# EEG_main.net
KiCad netlist of a schematic drawn in Altium Designer
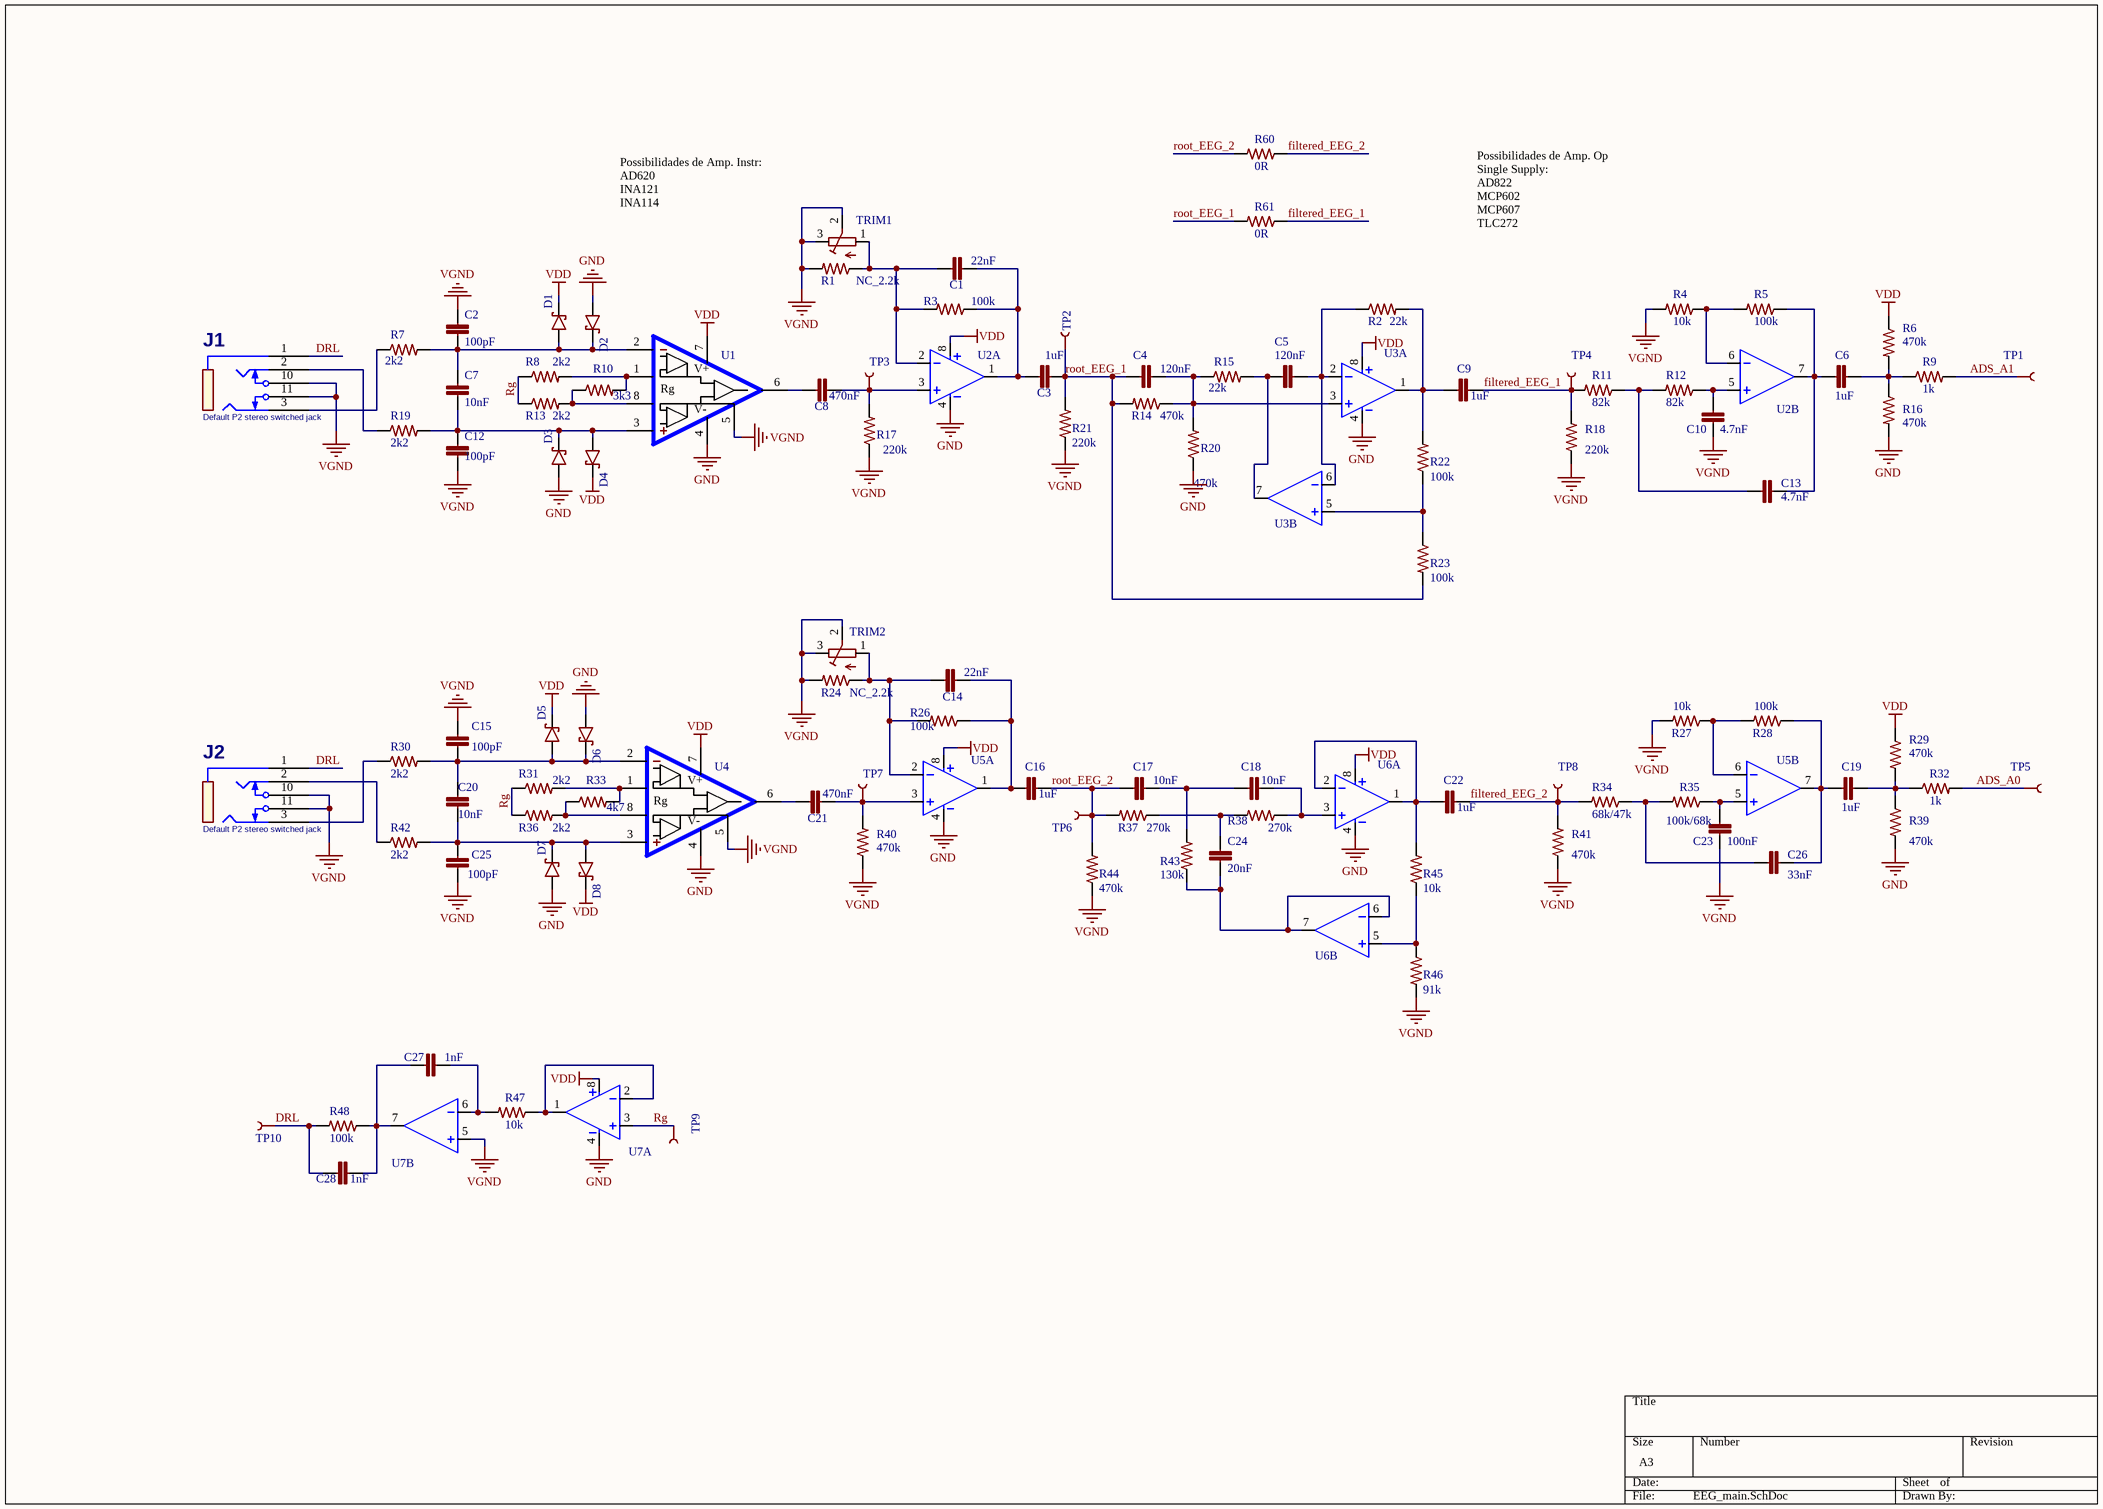
[diagram p0: EEG_main.SchDoc]

(export (version "E")
  (design (tool "Eeschema 10.0.6"))
  (components
    (comp (ref "C1")
      (value "22nF")
      (footprint "C0805 - rounded")
      (description "Generic Capacitor SMD")
      (libsource (lib "rcl") (part "C-EU-SMD"))
    )
    (comp (ref "C2")
      (value "100pF")
      (footprint "C0805 - rounded")
      (description "Generic Capacitor SMD")
      (libsource (lib "") (part "C-EU-SMD_1"))
    )
    (comp (ref "C3")
      (value "1uF")
      (footprint "C0805 - rounded")
      (description "Generic Capacitor SMD")
      (libsource (lib "rcl") (part "C-EU-SMD"))
    )
    (comp (ref "C4")
      (value "120nF")
      (footprint "C0805 - rounded")
      (description "Generic Capacitor SMD")
      (libsource (lib "rcl") (part "C-EU-SMD"))
    )
    (comp (ref "C5")
      (value "120nF")
      (footprint "C0805 - rounded")
      (description "Generic Capacitor SMD")
      (libsource (lib "rcl") (part "C-EU-SMD"))
    )
    (comp (ref "C6")
      (value "1uF")
      (footprint "C0805 - rounded")
      (description "Generic Capacitor SMD")
      (libsource (lib "rcl") (part "C-EU-SMD"))
    )
    (comp (ref "C7")
      (value "10nF")
      (footprint "C0805 - rounded")
      (description "Generic Capacitor SMD")
      (libsource (lib "") (part "C-EU-SMD_1"))
    )
    (comp (ref "C8")
      (value "470nF")
      (footprint "C0805 - rounded")
      (description "Generic Capacitor SMD")
      (libsource (lib "rcl") (part "C-EU-SMD"))
    )
    (comp (ref "C9")
      (value "1uF")
      (footprint "C0805 - rounded")
      (description "Generic Capacitor SMD")
      (libsource (lib "rcl") (part "C-EU-SMD"))
    )
    (comp (ref "C10")
      (value "4.7nF")
      (footprint "C0805 - rounded")
      (description "Generic Capacitor SMD")
      (libsource (lib "") (part "C-EU-SMD_1"))
    )
    (comp (ref "C12")
      (value "100pF")
      (footprint "C0805 - rounded")
      (description "Generic Capacitor SMD")
      (libsource (lib "") (part "C-EU-SMD_3"))
    )
    (comp (ref "C13")
      (value "4.7nF")
      (footprint "C0805 - rounded")
      (description "Generic Capacitor SMD")
      (libsource (lib "") (part "C-EU-SMD_2"))
    )
    (comp (ref "C14")
      (value "22nF")
      (footprint "C0805 - rounded")
      (description "Generic Capacitor SMD")
      (libsource (lib "rcl") (part "C-EU-SMD"))
    )
    (comp (ref "C15")
      (value "100pF")
      (footprint "C0805 - rounded")
      (description "Generic Capacitor SMD")
      (libsource (lib "") (part "C-EU-SMD_1"))
    )
    (comp (ref "C16")
      (value "1uF")
      (footprint "C0805 - rounded")
      (description "Generic Capacitor SMD")
      (libsource (lib "rcl") (part "C-EU-SMD"))
    )
    (comp (ref "C17")
      (value "10nF")
      (footprint "C0805 - rounded")
      (description "Generic Capacitor SMD")
      (libsource (lib "rcl") (part "C-EU-SMD"))
    )
    (comp (ref "C18")
      (value "10nF")
      (footprint "C0805 - rounded")
      (description "Generic Capacitor SMD")
      (libsource (lib "rcl") (part "C-EU-SMD"))
    )
    (comp (ref "C19")
      (value "1uF")
      (footprint "C0805 - rounded")
      (description "Generic Capacitor SMD")
      (libsource (lib "rcl") (part "C-EU-SMD"))
    )
    (comp (ref "C20")
      (value "10nF")
      (footprint "C0805 - rounded")
      (description "Generic Capacitor SMD")
      (libsource (lib "") (part "C-EU-SMD_1"))
    )
    (comp (ref "C21")
      (value "470nF")
      (footprint "C0805 - rounded")
      (description "Generic Capacitor SMD")
      (libsource (lib "rcl") (part "C-EU-SMD"))
    )
    (comp (ref "C22")
      (value "1uF")
      (footprint "C0805 - rounded")
      (description "Generic Capacitor SMD")
      (libsource (lib "rcl") (part "C-EU-SMD"))
    )
    (comp (ref "C23")
      (value "100nF")
      (footprint "C0805 - rounded")
      (description "Generic Capacitor SMD")
      (libsource (lib "") (part "C-EU-SMD_1"))
    )
    (comp (ref "C24")
      (value "20nF")
      (footprint "C0805 - rounded")
      (description "Generic Capacitor SMD")
      (libsource (lib "") (part "C-EU-SMD_1"))
    )
    (comp (ref "C25")
      (value "100pF")
      (footprint "C0805 - rounded")
      (description "Generic Capacitor SMD")
      (libsource (lib "") (part "C-EU-SMD_3"))
    )
    (comp (ref "C26")
      (value "33nF")
      (footprint "C0805 - rounded")
      (description "Generic Capacitor SMD")
      (libsource (lib "") (part "C-EU-SMD_2"))
    )
    (comp (ref "C27")
      (value "1nF")
      (footprint "C0805 - rounded")
      (description "Generic Capacitor SMD")
      (libsource (lib "rcl") (part "C-EU-SMD"))
    )
    (comp (ref "C28")
      (value "1nF")
      (footprint "C0805 - rounded")
      (description "Generic Capacitor SMD")
      (libsource (lib "rcl") (part "C-EU-SMD"))
    )
    (comp (ref "D1")
      (value "DIODE")
      (footprint "DO214AA")
      (fields (field (name "PART NUMBER") "SS12"))
      (libsource (lib "diode") (part "SCHOTTKY-DIODE"))
    )
    (comp (ref "D2")
      (value "DIODE")
      (footprint "DO214AA")
      (fields (field (name "PART NUMBER") "SS12"))
      (libsource (lib "diode") (part "SCHOTTKY-DIODE"))
    )
    (comp (ref "D3")
      (value "DIODE")
      (footprint "DO214AA")
      (fields (field (name "PART NUMBER") "SS12"))
      (libsource (lib "diode") (part "SCHOTTKY-DIODE"))
    )
    (comp (ref "D4")
      (value "DIODE")
      (footprint "DO214AA")
      (fields (field (name "PART NUMBER") "SS12"))
      (libsource (lib "diode") (part "SCHOTTKY-DIODE"))
    )
    (comp (ref "D5")
      (value "DIODE")
      (footprint "DO214AA")
      (fields (field (name "PART NUMBER") "SS12"))
      (libsource (lib "diode") (part "SCHOTTKY-DIODE"))
    )
    (comp (ref "D6")
      (value "DIODE")
      (footprint "DO214AA")
      (fields (field (name "PART NUMBER") "SS12"))
      (libsource (lib "diode") (part "SCHOTTKY-DIODE"))
    )
    (comp (ref "D7")
      (value "DIODE")
      (footprint "DO214AA")
      (fields (field (name "PART NUMBER") "SS12"))
      (libsource (lib "diode") (part "SCHOTTKY-DIODE"))
    )
    (comp (ref "D8")
      (value "DIODE")
      (footprint "DO214AA")
      (fields (field (name "PART NUMBER") "SS12"))
      (libsource (lib "diode") (part "SCHOTTKY-DIODE"))
    )
    (comp (ref "J1")
      (value "Default P2 stereo switched jack")
      (libsource (lib "Misc") (part "PHONEJACK - SJ1-352x"))
    )
    (comp (ref "J2")
      (value "Default P2 stereo switched jack")
      (libsource (lib "Misc") (part "PHONEJACK - SJ1-352x"))
    )
    (comp (ref "R1")
      (value "NC_2.2k")
      (footprint "R0805 - rounded")
      (description "Generic Resistor SMD")
      (libsource (lib "rcl") (part "R-US-SMD"))
    )
    (comp (ref "R2")
      (value "22k")
      (footprint "R0805 - rounded")
      (description "Generic Resistor SMD")
      (libsource (lib "rcl") (part "R-US-SMD"))
    )
    (comp (ref "R3")
      (value "100k")
      (footprint "R0805 - rounded")
      (description "Generic Resistor SMD")
      (libsource (lib "rcl") (part "R-US-SMD"))
    )
    (comp (ref "R4")
      (value "10k")
      (footprint "R0805 - rounded")
      (description "Generic Resistor SMD")
      (libsource (lib "rcl") (part "R-US-SMD"))
    )
    (comp (ref "R5")
      (value "100k")
      (footprint "R0805 - rounded")
      (description "Generic Resistor SMD")
      (libsource (lib "rcl") (part "R-US-SMD"))
    )
    (comp (ref "R6")
      (value "470k")
      (footprint "R0805 - rounded")
      (description "Generic Resistor SMD")
      (libsource (lib "rcl") (part "R-US-SMD"))
    )
    (comp (ref "R7")
      (value "2k2")
      (footprint "R0805 - rounded")
      (description "Generic Resistor SMD")
      (libsource (lib "rcl") (part "R-US-SMD"))
    )
    (comp (ref "R8")
      (value "2k2")
      (footprint "R0805 - rounded")
      (description "Generic Resistor SMD")
      (libsource (lib "rcl") (part "R-US-SMD"))
    )
    (comp (ref "R9")
      (value "1k")
      (footprint "R0805 - rounded")
      (description "Generic Resistor SMD")
      (libsource (lib "rcl") (part "R-US-SMD"))
    )
    (comp (ref "R10")
      (value "3k3")
      (footprint "R0805 - rounded")
      (description "Generic Resistor SMD")
      (libsource (lib "rcl") (part "R-US-SMD"))
    )
    (comp (ref "R11")
      (value "82k")
      (footprint "R0805 - rounded")
      (description "Generic Resistor SMD")
      (libsource (lib "rcl") (part "R-US-SMD"))
    )
    (comp (ref "R12")
      (value "82k")
      (footprint "R0805 - rounded")
      (description "Generic Resistor SMD")
      (libsource (lib "rcl") (part "R-US-SMD"))
    )
    (comp (ref "R13")
      (value "2k2")
      (footprint "R0805 - rounded")
      (description "Generic Resistor SMD")
      (libsource (lib "rcl") (part "R-US-SMD"))
    )
    (comp (ref "R14")
      (value "470k")
      (footprint "R0805 - rounded")
      (description "Generic Resistor SMD")
      (libsource (lib "rcl") (part "R-US-SMD"))
    )
    (comp (ref "R15")
      (value "22k")
      (footprint "R0805 - rounded")
      (description "Generic Resistor SMD")
      (libsource (lib "rcl") (part "R-US-SMD"))
    )
    (comp (ref "R16")
      (value "470k")
      (footprint "R0805 - rounded")
      (description "Generic Resistor SMD")
      (libsource (lib "rcl") (part "R-US-SMD"))
    )
    (comp (ref "R17")
      (value "220k")
      (footprint "R0805 - rounded")
      (description "Generic Resistor SMD")
      (libsource (lib "rcl") (part "R-US-SMD"))
    )
    (comp (ref "R18")
      (value "220k")
      (footprint "R0805 - rounded")
      (description "Generic Resistor SMD")
      (libsource (lib "rcl") (part "R-US-SMD"))
    )
    (comp (ref "R19")
      (value "2k2")
      (footprint "R0805 - rounded")
      (description "Generic Resistor SMD")
      (libsource (lib "rcl") (part "R-US-SMD"))
    )
    (comp (ref "R20")
      (value "470k")
      (footprint "R0805 - rounded")
      (description "Generic Resistor SMD")
      (libsource (lib "rcl") (part "R-US-SMD"))
    )
    (comp (ref "R21")
      (value "220k")
      (footprint "R0805 - rounded")
      (description "Generic Resistor SMD")
      (libsource (lib "rcl") (part "R-US-SMD"))
    )
    (comp (ref "R22")
      (value "100k")
      (footprint "R0805 - rounded")
      (description "Generic Resistor SMD")
      (libsource (lib "rcl") (part "R-US-SMD"))
    )
    (comp (ref "R23")
      (value "100k")
      (footprint "R0805 - rounded")
      (description "Generic Resistor SMD")
      (libsource (lib "rcl") (part "R-US-SMD"))
    )
    (comp (ref "R24")
      (value "NC_2.2k")
      (footprint "R0805 - rounded")
      (description "Generic Resistor SMD")
      (libsource (lib "rcl") (part "R-US-SMD"))
    )
    (comp (ref "R26")
      (value "100k")
      (footprint "R0805 - rounded")
      (description "Generic Resistor SMD")
      (libsource (lib "rcl") (part "R-US-SMD"))
    )
    (comp (ref "R27")
      (value "10k")
      (footprint "R0805 - rounded")
      (description "Generic Resistor SMD")
      (libsource (lib "rcl") (part "R-US-SMD"))
    )
    (comp (ref "R28")
      (value "100k")
      (footprint "R0805 - rounded")
      (description "Generic Resistor SMD")
      (libsource (lib "rcl") (part "R-US-SMD"))
    )
    (comp (ref "R29")
      (value "470k")
      (footprint "R0805 - rounded")
      (description "Generic Resistor SMD")
      (libsource (lib "rcl") (part "R-US-SMD"))
    )
    (comp (ref "R30")
      (value "2k2")
      (footprint "R0805 - rounded")
      (description "Generic Resistor SMD")
      (libsource (lib "rcl") (part "R-US-SMD"))
    )
    (comp (ref "R31")
      (value "2k2")
      (footprint "R0805 - rounded")
      (description "Generic Resistor SMD")
      (libsource (lib "rcl") (part "R-US-SMD"))
    )
    (comp (ref "R32")
      (value "1k")
      (footprint "R0805 - rounded")
      (description "Generic Resistor SMD")
      (libsource (lib "rcl") (part "R-US-SMD"))
    )
    (comp (ref "R33")
      (value "4k7")
      (footprint "R0805 - rounded")
      (description "Generic Resistor SMD")
      (libsource (lib "rcl") (part "R-US-SMD"))
    )
    (comp (ref "R34")
      (value "68k/47k")
      (footprint "R0805 - rounded")
      (description "Generic Resistor SMD")
      (libsource (lib "rcl") (part "R-US-SMD"))
    )
    (comp (ref "R35")
      (value "100k/68k")
      (footprint "R0805 - rounded")
      (description "Generic Resistor SMD")
      (libsource (lib "rcl") (part "R-US-SMD"))
    )
    (comp (ref "R36")
      (value "2k2")
      (footprint "R0805 - rounded")
      (description "Generic Resistor SMD")
      (libsource (lib "rcl") (part "R-US-SMD"))
    )
    (comp (ref "R37")
      (value "270k")
      (footprint "R0805 - rounded")
      (description "Generic Resistor SMD")
      (libsource (lib "rcl") (part "R-US-SMD"))
    )
    (comp (ref "R38")
      (value "270k")
      (footprint "R0805 - rounded")
      (description "Generic Resistor SMD")
      (libsource (lib "rcl") (part "R-US-SMD"))
    )
    (comp (ref "R39")
      (value "470k")
      (footprint "R0805 - rounded")
      (description "Generic Resistor SMD")
      (libsource (lib "rcl") (part "R-US-SMD"))
    )
    (comp (ref "R40")
      (value "470k")
      (footprint "R0805 - rounded")
      (description "Generic Resistor SMD")
      (libsource (lib "rcl") (part "R-US-SMD"))
    )
    (comp (ref "R41")
      (value "470k")
      (footprint "R0805 - rounded")
      (description "Generic Resistor SMD")
      (libsource (lib "rcl") (part "R-US-SMD"))
    )
    (comp (ref "R42")
      (value "2k2")
      (footprint "R0805 - rounded")
      (description "Generic Resistor SMD")
      (libsource (lib "rcl") (part "R-US-SMD"))
    )
    (comp (ref "R43")
      (value "130k")
      (footprint "R0805 - rounded")
      (description "Generic Resistor SMD")
      (libsource (lib "rcl") (part "R-US-SMD"))
    )
    (comp (ref "R44")
      (value "470k")
      (footprint "R0805 - rounded")
      (description "Generic Resistor SMD")
      (libsource (lib "rcl") (part "R-US-SMD"))
    )
    (comp (ref "R45")
      (value "10k")
      (footprint "R0805 - rounded")
      (description "Generic Resistor SMD")
      (libsource (lib "rcl") (part "R-US-SMD"))
    )
    (comp (ref "R46")
      (value "91k")
      (footprint "R0805 - rounded")
      (description "Generic Resistor SMD")
      (libsource (lib "rcl") (part "R-US-SMD"))
    )
    (comp (ref "R47")
      (value "10k")
      (footprint "R0805 - rounded")
      (description "Generic Resistor SMD")
      (libsource (lib "rcl") (part "R-US-SMD"))
    )
    (comp (ref "R48")
      (value "100k")
      (footprint "R0805 - rounded")
      (description "Generic Resistor SMD")
      (libsource (lib "rcl") (part "R-US-SMD"))
    )
    (comp (ref "R60")
      (value "0R")
      (footprint "R0805 - rounded")
      (description "Generic Resistor SMD")
      (libsource (lib "rcl") (part "R-US-SMD"))
    )
    (comp (ref "R61")
      (value "0R")
      (footprint "R0805 - rounded")
      (description "Generic Resistor SMD")
      (libsource (lib "rcl") (part "R-US-SMD"))
    )
    (comp (ref "TP1")
      (value "SparkFun Test Points    Bare copper test points for troubleshooting or In-Circuit-Testing. These are used by our Production team for verifying production board runs using pogo-pins on test beds.   SparkFun Products: SparkFun LSM9DS1 Breakout  SparkFun PSOC  SparkFun Load Cell Amplifier")
      (footprint "PAD.03X.03")
      (libsource (lib "Misc") (part "TEST-POINT2"))
    )
    (comp (ref "TP2")
      (value "SparkFun Test Points    Bare copper test points for troubleshooting or In-Circuit-Testing. These are used by our Production team for verifying production board runs using pogo-pins on test beds.   SparkFun Products: SparkFun LSM9DS1 Breakout  SparkFun PSOC  SparkFun Load Cell Amplifier")
      (footprint "PAD.03X.03")
      (libsource (lib "Misc") (part "TEST-POINT2"))
    )
    (comp (ref "TP3")
      (value "SparkFun Test Points    Bare copper test points for troubleshooting or In-Circuit-Testing. These are used by our Production team for verifying production board runs using pogo-pins on test beds.   SparkFun Products: SparkFun LSM9DS1 Breakout  SparkFun PSOC  SparkFun Load Cell Amplifier")
      (footprint "PAD.03X.03")
      (libsource (lib "Misc") (part "TEST-POINT2"))
    )
    (comp (ref "TP4")
      (value "SparkFun Test Points    Bare copper test points for troubleshooting or In-Circuit-Testing. These are used by our Production team for verifying production board runs using pogo-pins on test beds.   SparkFun Products: SparkFun LSM9DS1 Breakout  SparkFun PSOC  SparkFun Load Cell Amplifier")
      (footprint "PAD.03X.03")
      (libsource (lib "Misc") (part "TEST-POINT2"))
    )
    (comp (ref "TP5")
      (value "SparkFun Test Points    Bare copper test points for troubleshooting or In-Circuit-Testing. These are used by our Production team for verifying production board runs using pogo-pins on test beds.   SparkFun Products: SparkFun LSM9DS1 Breakout  SparkFun PSOC  SparkFun Load Cell Amplifier")
      (footprint "PAD.03X.03")
      (libsource (lib "Misc") (part "TEST-POINT2"))
    )
    (comp (ref "TP6")
      (value "SparkFun Test Points    Bare copper test points for troubleshooting or In-Circuit-Testing. These are used by our Production team for verifying production board runs using pogo-pins on test beds.   SparkFun Products: SparkFun LSM9DS1 Breakout  SparkFun PSOC  SparkFun Load Cell Amplifier")
      (footprint "PAD.03X.03")
      (libsource (lib "Misc") (part "TEST-POINT2"))
    )
    (comp (ref "TP7")
      (value "SparkFun Test Points    Bare copper test points for troubleshooting or In-Circuit-Testing. These are used by our Production team for verifying production board runs using pogo-pins on test beds.   SparkFun Products: SparkFun LSM9DS1 Breakout  SparkFun PSOC  SparkFun Load Cell Amplifier")
      (footprint "PAD.03X.03")
      (libsource (lib "Misc") (part "TEST-POINT2"))
    )
    (comp (ref "TP8")
      (value "SparkFun Test Points    Bare copper test points for troubleshooting or In-Circuit-Testing. These are used by our Production team for verifying production board runs using pogo-pins on test beds.   SparkFun Products: SparkFun LSM9DS1 Breakout  SparkFun PSOC  SparkFun Load Cell Amplifier")
      (footprint "PAD.03X.03")
      (libsource (lib "Misc") (part "TEST-POINT2"))
    )
    (comp (ref "TP9")
      (value "SparkFun Test Points    Bare copper test points for troubleshooting or In-Circuit-Testing. These are used by our Production team for verifying production board runs using pogo-pins on test beds.   SparkFun Products: SparkFun LSM9DS1 Breakout  SparkFun PSOC  SparkFun Load Cell Amplifier")
      (footprint "PAD.03X.03")
      (libsource (lib "Misc") (part "TEST-POINT2"))
    )
    (comp (ref "TP10")
      (value "SparkFun Test Points    Bare copper test points for troubleshooting or In-Circuit-Testing. These are used by our Production team for verifying production board runs using pogo-pins on test beds.   SparkFun Products: SparkFun LSM9DS1 Breakout  SparkFun PSOC  SparkFun Load Cell Amplifier")
      (footprint "PAD.03X.03")
      (libsource (lib "Misc") (part "TEST-POINT2"))
    )
    (comp (ref "TRIM1") (value "R-TRIMM") (footprint "RTRIM3386") (libsource (lib "rcl") (part "R-TRIMM")))
    (comp (ref "TRIM2") (value "R-TRIMM") (footprint "RTRIM3386") (libsource (lib "rcl") (part "R-TRIMM")))
    (comp (ref "U1")
      (value "AD620")
      (footprint "SOIC8")
      (description "Low Cost Low Power Instrumentation Amplifier")
      (libsource (lib "amplifiers") (part "AD620"))
    )
    (comp (ref "U2")
      (value "MCP602")
      (footprint "SOIC8")
      (description "Operational Amplifiers - Op Amps Dual 2.7V")
      (libsource (lib "amplifiers") (part "MCP602"))
    )
    (comp (ref "U3")
      (value "MCP602")
      (footprint "SOIC8")
      (description "Operational Amplifiers - Op Amps Dual 2.7V")
      (libsource (lib "amplifiers") (part "MCP602"))
    )
    (comp (ref "U4")
      (value "AD620")
      (footprint "SOIC8")
      (description "Low Cost Low Power Instrumentation Amplifier")
      (libsource (lib "amplifiers") (part "AD620"))
    )
    (comp (ref "U5")
      (value "MCP602")
      (footprint "SOIC8")
      (description "Operational Amplifiers - Op Amps Dual 2.7V")
      (libsource (lib "amplifiers") (part "MCP602"))
    )
    (comp (ref "U6")
      (value "MCP602")
      (footprint "SOIC8")
      (description "Operational Amplifiers - Op Amps Dual 2.7V")
      (libsource (lib "amplifiers") (part "MCP602"))
    )
    (comp (ref "U7")
      (value "MCP602")
      (footprint "SOIC8")
      (description "Wide Bandwidth Dual JFET Input Op Amp")
      (libsource (lib "amplifiers") (part "TL082"))
    )
  )
  (nets
    (net (code "1") (name "/ADS_A0") (class "Default")
      (node (ref "R32") (pin "2") (pinfunction "2_2") (pintype "passive"))
      (node (ref "TP5") (pin "P$1") (pinfunction "1_P$1") (pintype "passive"))
    )
    (net (code "2") (name "/ADS_A1") (class "Default")
      (node (ref "R9") (pin "2") (pinfunction "2_2") (pintype "passive"))
      (node (ref "TP1") (pin "P$1") (pinfunction "1_P$1") (pintype "passive"))
    )
    (net (code "3") (name "/DRL") (class "Default")
      (node (ref "C28") (pin "1") (pinfunction "1_1") (pintype "passive"))
      (node (ref "J1") (pin "1") (pinfunction "SLEEVE_1") (pintype "passive"))
      (node (ref "J2") (pin "1") (pinfunction "SLEEVE_1") (pintype "passive"))
      (node (ref "R48") (pin "2") (pinfunction "2_2") (pintype "passive"))
      (node (ref "TP10") (pin "P$1") (pinfunction "1_P$1") (pintype "passive"))
    )
    (net (code "4") (name "/Rg") (class "Default")
      (node (ref "R13") (pin "1") (pinfunction "1_1") (pintype "passive"))
      (node (ref "R31") (pin "1") (pinfunction "1_1") (pintype "passive"))
      (node (ref "R36") (pin "1") (pinfunction "1_1") (pintype "passive"))
      (node (ref "R8") (pin "1") (pinfunction "1_1") (pintype "passive"))
      (node (ref "TP9") (pin "P$1") (pinfunction "1_P$1") (pintype "passive"))
      (node (ref "U7") (pin "3") (pinfunction "+IN_3") (pintype "passive"))
    )
    (net (code "5") (name "/filtered_EEG_1") (class "Default")
      (node (ref "C9") (pin "2") (pinfunction "2_2") (pintype "passive"))
      (node (ref "R11") (pin "2") (pinfunction "2_2") (pintype "passive"))
      (node (ref "R18") (pin "2") (pinfunction "2_2") (pintype "passive"))
      (node (ref "R61") (pin "1") (pinfunction "1_1") (pintype "passive"))
      (node (ref "TP4") (pin "P$1") (pinfunction "1_P$1") (pintype "passive"))
    )
    (net (code "6") (name "/filtered_EEG_2") (class "Default")
      (node (ref "C22") (pin "2") (pinfunction "2_2") (pintype "passive"))
      (node (ref "R34") (pin "2") (pinfunction "2_2") (pintype "passive"))
      (node (ref "R41") (pin "2") (pinfunction "2_2") (pintype "passive"))
      (node (ref "R60") (pin "1") (pinfunction "1_1") (pintype "passive"))
      (node (ref "TP8") (pin "P$1") (pinfunction "1_P$1") (pintype "passive"))
    )
    (net (code "7") (name "/root_EEG_1") (class "Default")
      (node (ref "C3") (pin "2") (pinfunction "2_2") (pintype "passive"))
      (node (ref "C4") (pin "1") (pinfunction "1_1") (pintype "passive"))
      (node (ref "R14") (pin "2") (pinfunction "2_2") (pintype "passive"))
      (node (ref "R21") (pin "2") (pinfunction "2_2") (pintype "passive"))
      (node (ref "R23") (pin "2") (pinfunction "2_2") (pintype "passive"))
      (node (ref "R61") (pin "2") (pinfunction "2_2") (pintype "passive"))
      (node (ref "TP2") (pin "P$1") (pinfunction "1_P$1") (pintype "passive"))
    )
    (net (code "8") (name "/root_EEG_2") (class "Default")
      (node (ref "C16") (pin "2") (pinfunction "2_2") (pintype "passive"))
      (node (ref "C17") (pin "1") (pinfunction "1_1") (pintype "passive"))
      (node (ref "R37") (pin "2") (pinfunction "2_2") (pintype "passive"))
      (node (ref "R44") (pin "2") (pinfunction "2_2") (pintype "passive"))
      (node (ref "R60") (pin "2") (pinfunction "2_2") (pintype "passive"))
      (node (ref "TP6") (pin "P$1") (pinfunction "1_P$1") (pintype "passive"))
    )
    (net (code "9") (name "GND") (class "Default")
      (node (ref "D2") (pin "A") (pinfunction "A_A") (pintype "passive"))
      (node (ref "D3") (pin "A") (pinfunction "A_A") (pintype "passive"))
      (node (ref "D6") (pin "A") (pinfunction "A_A") (pintype "passive"))
      (node (ref "D7") (pin "A") (pinfunction "A_A") (pintype "passive"))
      (node (ref "R16") (pin "2") (pinfunction "2_2") (pintype "passive"))
      (node (ref "R20") (pin "1") (pinfunction "1_1") (pintype "passive"))
      (node (ref "R39") (pin "2") (pinfunction "2_2") (pintype "passive"))
      (node (ref "U1") (pin "4") (pinfunction "V-_4") (pintype "power_in"))
      (node (ref "U2") (pin "4") (pinfunction "V-_4") (pintype "power_in"))
      (node (ref "U3") (pin "4") (pinfunction "V-_4") (pintype "power_in"))
      (node (ref "U4") (pin "4") (pinfunction "V-_4") (pintype "power_in"))
      (node (ref "U5") (pin "4") (pinfunction "V-_4") (pintype "power_in"))
      (node (ref "U6") (pin "4") (pinfunction "V-_4") (pintype "power_in"))
      (node (ref "U7") (pin "4") (pinfunction "V-_4") (pintype "power_in"))
    )
    (net (code "10") (name "Net-(C6-Pad2)") (class "Default")
      (node (ref "C6") (pin "2") (pinfunction "2_2") (pintype "passive"))
      (node (ref "R16") (pin "1") (pinfunction "1_1") (pintype "passive"))
      (node (ref "R6") (pin "2") (pinfunction "2_2") (pintype "passive"))
      (node (ref "R9") (pin "1") (pinfunction "1_1") (pintype "passive"))
    )
    (net (code "11") (name "Net-(C13-Pad2)") (class "Default")
      (node (ref "C13") (pin "2") (pinfunction "2_2") (pintype "passive"))
      (node (ref "R11") (pin "1") (pinfunction "1_1") (pintype "passive"))
      (node (ref "R12") (pin "2") (pinfunction "2_2") (pintype "passive"))
    )
    (net (code "12") (name "Net-(C17-Pad2)") (class "Default")
      (node (ref "C17") (pin "2") (pinfunction "2_2") (pintype "passive"))
      (node (ref "C18") (pin "1") (pinfunction "1_1") (pintype "passive"))
      (node (ref "R43") (pin "2") (pinfunction "2_2") (pintype "passive"))
    )
    (net (code "13") (name "Net-(C19-Pad2)") (class "Default")
      (node (ref "C19") (pin "2") (pinfunction "2_2") (pintype "passive"))
      (node (ref "R29") (pin "2") (pinfunction "2_2") (pintype "passive"))
      (node (ref "R32") (pin "1") (pinfunction "1_1") (pintype "passive"))
      (node (ref "R39") (pin "1") (pinfunction "1_1") (pintype "passive"))
    )
    (net (code "14") (name "Net-(C24-Pad2)") (class "Default")
      (node (ref "C24") (pin "2") (pinfunction "2_2") (pintype "passive"))
      (node (ref "R37") (pin "1") (pinfunction "1_1") (pintype "passive"))
      (node (ref "R38") (pin "2") (pinfunction "2_2") (pintype "passive"))
    )
    (net (code "15") (name "Net-(C26-Pad2)") (class "Default")
      (node (ref "C26") (pin "2") (pinfunction "2_2") (pintype "passive"))
      (node (ref "R34") (pin "1") (pinfunction "1_1") (pintype "passive"))
      (node (ref "R35") (pin "2") (pinfunction "2_2") (pintype "passive"))
    )
    (net (code "16") (name "Net-(J1-RING)") (class "Default")
      (node (ref "J1") (pin "3") (pinfunction "RING_3") (pintype "passive"))
      (node (ref "R7") (pin "1") (pinfunction "1_1") (pintype "passive"))
    )
    (net (code "17") (name "Net-(J1-TIP)") (class "Default")
      (node (ref "J1") (pin "2") (pinfunction "TIP_2") (pintype "passive"))
      (node (ref "R19") (pin "1") (pinfunction "1_1") (pintype "passive"))
    )
    (net (code "18") (name "Net-(J2-RING)") (class "Default")
      (node (ref "J2") (pin "3") (pinfunction "RING_3") (pintype "passive"))
      (node (ref "R30") (pin "1") (pinfunction "1_1") (pintype "passive"))
    )
    (net (code "19") (name "Net-(J2-TIP)") (class "Default")
      (node (ref "J2") (pin "2") (pinfunction "TIP_2") (pintype "passive"))
      (node (ref "R42") (pin "1") (pinfunction "1_1") (pintype "passive"))
    )
    (net (code "20") (name "Net-(R10-Pad1)") (class "Default")
      (node (ref "R10") (pin "1") (pinfunction "1_1") (pintype "passive"))
      (node (ref "R13") (pin "2") (pinfunction "2_2") (pintype "passive"))
      (node (ref "U1") (pin "8") (pinfunction "Rg_8") (pintype "passive"))
    )
    (net (code "21") (name "Net-(R10-Pad2)") (class "Default")
      (node (ref "R10") (pin "2") (pinfunction "2_2") (pintype "passive"))
      (node (ref "R8") (pin "2") (pinfunction "2_2") (pintype "passive"))
      (node (ref "U1") (pin "1") (pinfunction "Rg_1") (pintype "passive"))
    )
    (net (code "22") (name "Net-(R31-Pad2)") (class "Default")
      (node (ref "R31") (pin "2") (pinfunction "2_2") (pintype "passive"))
      (node (ref "R33") (pin "2") (pinfunction "2_2") (pintype "passive"))
      (node (ref "U4") (pin "1") (pinfunction "Rg_1") (pintype "passive"))
    )
    (net (code "23") (name "Net-(R33-Pad1)") (class "Default")
      (node (ref "R33") (pin "1") (pinfunction "1_1") (pintype "passive"))
      (node (ref "R36") (pin "2") (pinfunction "2_2") (pintype "passive"))
      (node (ref "U4") (pin "8") (pinfunction "Rg_8") (pintype "passive"))
    )
    (net (code "24") (name "Net-(TP3-1)") (class "Default")
      (node (ref "C8") (pin "2") (pinfunction "2_2") (pintype "passive"))
      (node (ref "R17") (pin "2") (pinfunction "2_2") (pintype "passive"))
      (node (ref "TP3") (pin "P$1") (pinfunction "1_P$1") (pintype "passive"))
      (node (ref "U2") (pin "3") (pinfunction "+IN_3") (pintype "passive"))
    )
    (net (code "25") (name "Net-(TP7-1)") (class "Default")
      (node (ref "C21") (pin "2") (pinfunction "2_2") (pintype "passive"))
      (node (ref "R40") (pin "2") (pinfunction "2_2") (pintype "passive"))
      (node (ref "TP7") (pin "P$1") (pinfunction "1_P$1") (pintype "passive"))
      (node (ref "U5") (pin "3") (pinfunction "+IN_3") (pintype "passive"))
    )
    (net (code "26") (name "Net-(TRIM1-A)") (class "Default")
      (node (ref "C1") (pin "1") (pinfunction "1_1") (pintype "passive"))
      (node (ref "R1") (pin "1") (pinfunction "1_1") (pintype "passive"))
      (node (ref "R3") (pin "2") (pinfunction "2_2") (pintype "passive"))
      (node (ref "TRIM1") (pin "1") (pinfunction "A_1") (pintype "passive"))
      (node (ref "U2") (pin "2") (pinfunction "-IN_2") (pintype "passive"))
    )
    (net (code "27") (name "Net-(TRIM2-A)") (class "Default")
      (node (ref "C14") (pin "1") (pinfunction "1_1") (pintype "passive"))
      (node (ref "R24") (pin "1") (pinfunction "1_1") (pintype "passive"))
      (node (ref "R26") (pin "2") (pinfunction "2_2") (pintype "passive"))
      (node (ref "TRIM2") (pin "1") (pinfunction "A_1") (pintype "passive"))
      (node (ref "U5") (pin "2") (pinfunction "-IN_2") (pintype "passive"))
    )
    (net (code "28") (name "Net-(U1-+IN)") (class "Default")
      (node (ref "C12") (pin "1") (pinfunction "1_1") (pintype "passive"))
      (node (ref "C7") (pin "1") (pinfunction "1_1") (pintype "passive"))
      (node (ref "D3") (pin "C") (pinfunction "C_C") (pintype "passive"))
      (node (ref "D4") (pin "A") (pinfunction "A_A") (pintype "passive"))
      (node (ref "R19") (pin "2") (pinfunction "2_2") (pintype "passive"))
      (node (ref "U1") (pin "3") (pinfunction "+IN_3") (pintype "passive"))
    )
    (net (code "29") (name "Net-(U1--IN)") (class "Default")
      (node (ref "C2") (pin "1") (pinfunction "1_1") (pintype "passive"))
      (node (ref "C7") (pin "2") (pinfunction "2_2") (pintype "passive"))
      (node (ref "D1") (pin "A") (pinfunction "A_A") (pintype "passive"))
      (node (ref "D2") (pin "C") (pinfunction "C_C") (pintype "passive"))
      (node (ref "R7") (pin "2") (pinfunction "2_2") (pintype "passive"))
      (node (ref "U1") (pin "2") (pinfunction "-IN_2") (pintype "passive"))
    )
    (net (code "30") (name "Net-(U1-OUT)") (class "Default")
      (node (ref "C8") (pin "1") (pinfunction "1_1") (pintype "passive"))
      (node (ref "U1") (pin "6") (pinfunction "OUT_6") (pintype "passive"))
    )
    (net (code "31") (name "Net-(U2A-OUT)") (class "Default")
      (node (ref "C1") (pin "2") (pinfunction "2_2") (pintype "passive"))
      (node (ref "C3") (pin "1") (pinfunction "1_1") (pintype "passive"))
      (node (ref "R3") (pin "1") (pinfunction "1_1") (pintype "passive"))
      (node (ref "U2") (pin "1") (pinfunction "OUT_1") (pintype "passive"))
    )
    (net (code "32") (name "Net-(U2B-+IN)") (class "Default")
      (node (ref "C10") (pin "2") (pinfunction "2_2") (pintype "passive"))
      (node (ref "R12") (pin "1") (pinfunction "1_1") (pintype "passive"))
      (node (ref "U2") (pin "5") (pinfunction "+IN_5") (pintype "passive"))
    )
    (net (code "33") (name "Net-(U2B--IN)") (class "Default")
      (node (ref "R4") (pin "1") (pinfunction "1_1") (pintype "passive"))
      (node (ref "R5") (pin "2") (pinfunction "2_2") (pintype "passive"))
      (node (ref "U2") (pin "6") (pinfunction "-IN_6") (pintype "passive"))
    )
    (net (code "34") (name "Net-(U2B-OUT)") (class "Default")
      (node (ref "C13") (pin "1") (pinfunction "1_1") (pintype "passive"))
      (node (ref "C6") (pin "1") (pinfunction "1_1") (pintype "passive"))
      (node (ref "R5") (pin "1") (pinfunction "1_1") (pintype "passive"))
      (node (ref "U2") (pin "7") (pinfunction "OUT_7") (pintype "passive"))
    )
    (net (code "35") (name "Net-(U3A-+IN)") (class "Default")
      (node (ref "C4") (pin "2") (pinfunction "2_2") (pintype "passive"))
      (node (ref "R14") (pin "1") (pinfunction "1_1") (pintype "passive"))
      (node (ref "R15") (pin "1") (pinfunction "1_1") (pintype "passive"))
      (node (ref "R20") (pin "2") (pinfunction "2_2") (pintype "passive"))
      (node (ref "U3") (pin "3") (pinfunction "+IN_3") (pintype "passive"))
    )
    (net (code "36") (name "Net-(U3A--IN)") (class "Default")
      (node (ref "C5") (pin "2") (pinfunction "2_2") (pintype "passive"))
      (node (ref "R2") (pin "1") (pinfunction "1_1") (pintype "passive"))
      (node (ref "U3") (pin "2") (pinfunction "-IN_2") (pintype "passive"))
      (node (ref "U3") (pin "6") (pinfunction "-IN_6") (pintype "passive"))
    )
    (net (code "37") (name "Net-(U3A-OUT)") (class "Default")
      (node (ref "C9") (pin "1") (pinfunction "1_1") (pintype "passive"))
      (node (ref "R2") (pin "2") (pinfunction "2_2") (pintype "passive"))
      (node (ref "R22") (pin "2") (pinfunction "2_2") (pintype "passive"))
      (node (ref "U3") (pin "1") (pinfunction "OUT_1") (pintype "passive"))
    )
    (net (code "38") (name "Net-(U3B-+IN)") (class "Default")
      (node (ref "R22") (pin "1") (pinfunction "1_1") (pintype "passive"))
      (node (ref "R23") (pin "1") (pinfunction "1_1") (pintype "passive"))
      (node (ref "U3") (pin "5") (pinfunction "+IN_5") (pintype "passive"))
    )
    (net (code "39") (name "Net-(U3B-OUT)") (class "Default")
      (node (ref "C5") (pin "1") (pinfunction "1_1") (pintype "passive"))
      (node (ref "R15") (pin "2") (pinfunction "2_2") (pintype "passive"))
      (node (ref "U3") (pin "7") (pinfunction "OUT_7") (pintype "passive"))
    )
    (net (code "40") (name "Net-(U4-+IN)") (class "Default")
      (node (ref "C20") (pin "1") (pinfunction "1_1") (pintype "passive"))
      (node (ref "C25") (pin "1") (pinfunction "1_1") (pintype "passive"))
      (node (ref "D7") (pin "C") (pinfunction "C_C") (pintype "passive"))
      (node (ref "D8") (pin "A") (pinfunction "A_A") (pintype "passive"))
      (node (ref "R42") (pin "2") (pinfunction "2_2") (pintype "passive"))
      (node (ref "U4") (pin "3") (pinfunction "+IN_3") (pintype "passive"))
    )
    (net (code "41") (name "Net-(U4--IN)") (class "Default")
      (node (ref "C15") (pin "1") (pinfunction "1_1") (pintype "passive"))
      (node (ref "C20") (pin "2") (pinfunction "2_2") (pintype "passive"))
      (node (ref "D5") (pin "A") (pinfunction "A_A") (pintype "passive"))
      (node (ref "D6") (pin "C") (pinfunction "C_C") (pintype "passive"))
      (node (ref "R30") (pin "2") (pinfunction "2_2") (pintype "passive"))
      (node (ref "U4") (pin "2") (pinfunction "-IN_2") (pintype "passive"))
    )
    (net (code "42") (name "Net-(U4-OUT)") (class "Default")
      (node (ref "C21") (pin "1") (pinfunction "1_1") (pintype "passive"))
      (node (ref "U4") (pin "6") (pinfunction "OUT_6") (pintype "passive"))
    )
    (net (code "43") (name "Net-(U5A-OUT)") (class "Default")
      (node (ref "C14") (pin "2") (pinfunction "2_2") (pintype "passive"))
      (node (ref "C16") (pin "1") (pinfunction "1_1") (pintype "passive"))
      (node (ref "R26") (pin "1") (pinfunction "1_1") (pintype "passive"))
      (node (ref "U5") (pin "1") (pinfunction "OUT_1") (pintype "passive"))
    )
    (net (code "44") (name "Net-(U5B-+IN)") (class "Default")
      (node (ref "C23") (pin "2") (pinfunction "2_2") (pintype "passive"))
      (node (ref "R35") (pin "1") (pinfunction "1_1") (pintype "passive"))
      (node (ref "U5") (pin "5") (pinfunction "+IN_5") (pintype "passive"))
    )
    (net (code "45") (name "Net-(U5B--IN)") (class "Default")
      (node (ref "R27") (pin "1") (pinfunction "1_1") (pintype "passive"))
      (node (ref "R28") (pin "2") (pinfunction "2_2") (pintype "passive"))
      (node (ref "U5") (pin "6") (pinfunction "-IN_6") (pintype "passive"))
    )
    (net (code "46") (name "Net-(U5B-OUT)") (class "Default")
      (node (ref "C19") (pin "1") (pinfunction "1_1") (pintype "passive"))
      (node (ref "C26") (pin "1") (pinfunction "1_1") (pintype "passive"))
      (node (ref "R28") (pin "1") (pinfunction "1_1") (pintype "passive"))
      (node (ref "U5") (pin "7") (pinfunction "OUT_7") (pintype "passive"))
    )
    (net (code "47") (name "Net-(U6A-+IN)") (class "Default")
      (node (ref "C18") (pin "2") (pinfunction "2_2") (pintype "passive"))
      (node (ref "R38") (pin "1") (pinfunction "1_1") (pintype "passive"))
      (node (ref "U6") (pin "3") (pinfunction "+IN_3") (pintype "passive"))
    )
    (net (code "48") (name "Net-(U6A--IN)") (class "Default")
      (node (ref "C22") (pin "1") (pinfunction "1_1") (pintype "passive"))
      (node (ref "R45") (pin "2") (pinfunction "2_2") (pintype "passive"))
      (node (ref "U6") (pin "1") (pinfunction "OUT_1") (pintype "passive"))
      (node (ref "U6") (pin "2") (pinfunction "-IN_2") (pintype "passive"))
    )
    (net (code "49") (name "Net-(U6B-+IN)") (class "Default")
      (node (ref "R45") (pin "1") (pinfunction "1_1") (pintype "passive"))
      (node (ref "R46") (pin "1") (pinfunction "1_1") (pintype "passive"))
      (node (ref "U6") (pin "5") (pinfunction "+IN_5") (pintype "passive"))
    )
    (net (code "50") (name "Net-(U6B--IN)") (class "Default")
      (node (ref "C24") (pin "1") (pinfunction "1_1") (pintype "passive"))
      (node (ref "R43") (pin "1") (pinfunction "1_1") (pintype "passive"))
      (node (ref "U6") (pin "6") (pinfunction "-IN_6") (pintype "passive"))
      (node (ref "U6") (pin "7") (pinfunction "OUT_7") (pintype "passive"))
    )
    (net (code "51") (name "Net-(U7A--IN)") (class "Default")
      (node (ref "R47") (pin "1") (pinfunction "1_1") (pintype "passive"))
      (node (ref "U7") (pin "1") (pinfunction "OUT_1") (pintype "passive"))
      (node (ref "U7") (pin "2") (pinfunction "-IN_2") (pintype "passive"))
    )
    (net (code "52") (name "Net-(U7B--IN)") (class "Default")
      (node (ref "C27") (pin "2") (pinfunction "2_2") (pintype "passive"))
      (node (ref "R47") (pin "2") (pinfunction "2_2") (pintype "passive"))
      (node (ref "U7") (pin "6") (pinfunction "-IN_6") (pintype "passive"))
    )
    (net (code "53") (name "Net-(U7B-OUT)") (class "Default")
      (node (ref "C27") (pin "1") (pinfunction "1_1") (pintype "passive"))
      (node (ref "C28") (pin "2") (pinfunction "2_2") (pintype "passive"))
      (node (ref "R48") (pin "1") (pinfunction "1_1") (pintype "passive"))
      (node (ref "U7") (pin "7") (pinfunction "OUT_7") (pintype "passive"))
    )
    (net (code "54") (name "VDD") (class "Default")
      (node (ref "D1") (pin "C") (pinfunction "C_C") (pintype "passive"))
      (node (ref "D4") (pin "C") (pinfunction "C_C") (pintype "passive"))
      (node (ref "D5") (pin "C") (pinfunction "C_C") (pintype "passive"))
      (node (ref "D8") (pin "C") (pinfunction "C_C") (pintype "passive"))
      (node (ref "R29") (pin "1") (pinfunction "1_1") (pintype "passive"))
      (node (ref "R6") (pin "1") (pinfunction "1_1") (pintype "passive"))
      (node (ref "U1") (pin "7") (pinfunction "V+_7") (pintype "power_in"))
      (node (ref "U2") (pin "8") (pinfunction "V+_8") (pintype "power_in"))
      (node (ref "U3") (pin "8") (pinfunction "V+_8") (pintype "power_in"))
      (node (ref "U4") (pin "7") (pinfunction "V+_7") (pintype "power_in"))
      (node (ref "U5") (pin "8") (pinfunction "V+_8") (pintype "power_in"))
      (node (ref "U6") (pin "8") (pinfunction "V+_8") (pintype "power_in"))
      (node (ref "U7") (pin "8") (pinfunction "V+_8") (pintype "power_in"))
    )
    (net (code "55") (name "VGND") (class "Default")
      (node (ref "C10") (pin "1") (pinfunction "1_1") (pintype "passive"))
      (node (ref "C12") (pin "2") (pinfunction "2_2") (pintype "passive"))
      (node (ref "C15") (pin "2") (pinfunction "2_2") (pintype "passive"))
      (node (ref "C2") (pin "2") (pinfunction "2_2") (pintype "passive"))
      (node (ref "C23") (pin "1") (pinfunction "1_1") (pintype "passive"))
      (node (ref "C25") (pin "2") (pinfunction "2_2") (pintype "passive"))
      (node (ref "J1") (pin "10") (pinfunction "TIP_SW_10") (pintype "passive"))
      (node (ref "J1") (pin "11") (pinfunction "RING_SW_11") (pintype "passive"))
      (node (ref "J2") (pin "10") (pinfunction "TIP_SW_10") (pintype "passive"))
      (node (ref "J2") (pin "11") (pinfunction "RING_SW_11") (pintype "passive"))
      (node (ref "R1") (pin "2") (pinfunction "2_2") (pintype "passive"))
      (node (ref "R17") (pin "1") (pinfunction "1_1") (pintype "passive"))
      (node (ref "R18") (pin "1") (pinfunction "1_1") (pintype "passive"))
      (node (ref "R21") (pin "1") (pinfunction "1_1") (pintype "passive"))
      (node (ref "R24") (pin "2") (pinfunction "2_2") (pintype "passive"))
      (node (ref "R27") (pin "2") (pinfunction "2_2") (pintype "passive"))
      (node (ref "R4") (pin "2") (pinfunction "2_2") (pintype "passive"))
      (node (ref "R40") (pin "1") (pinfunction "1_1") (pintype "passive"))
      (node (ref "R41") (pin "1") (pinfunction "1_1") (pintype "passive"))
      (node (ref "R44") (pin "1") (pinfunction "1_1") (pintype "passive"))
      (node (ref "R46") (pin "2") (pinfunction "2_2") (pintype "passive"))
      (node (ref "TRIM1") (pin "2") (pinfunction "S_2") (pintype "passive"))
      (node (ref "TRIM1") (pin "3") (pinfunction "E_3") (pintype "passive"))
      (node (ref "TRIM2") (pin "2") (pinfunction "S_2") (pintype "passive"))
      (node (ref "TRIM2") (pin "3") (pinfunction "E_3") (pintype "passive"))
      (node (ref "U1") (pin "5") (pinfunction "REF_5") (pintype "power_in"))
      (node (ref "U4") (pin "5") (pinfunction "REF_5") (pintype "power_in"))
      (node (ref "U7") (pin "5") (pinfunction "+IN_5") (pintype "passive"))
    )
  )
)
